# WR-Clocks.net
KiCad netlist of a schematic drawn in Altium Designer
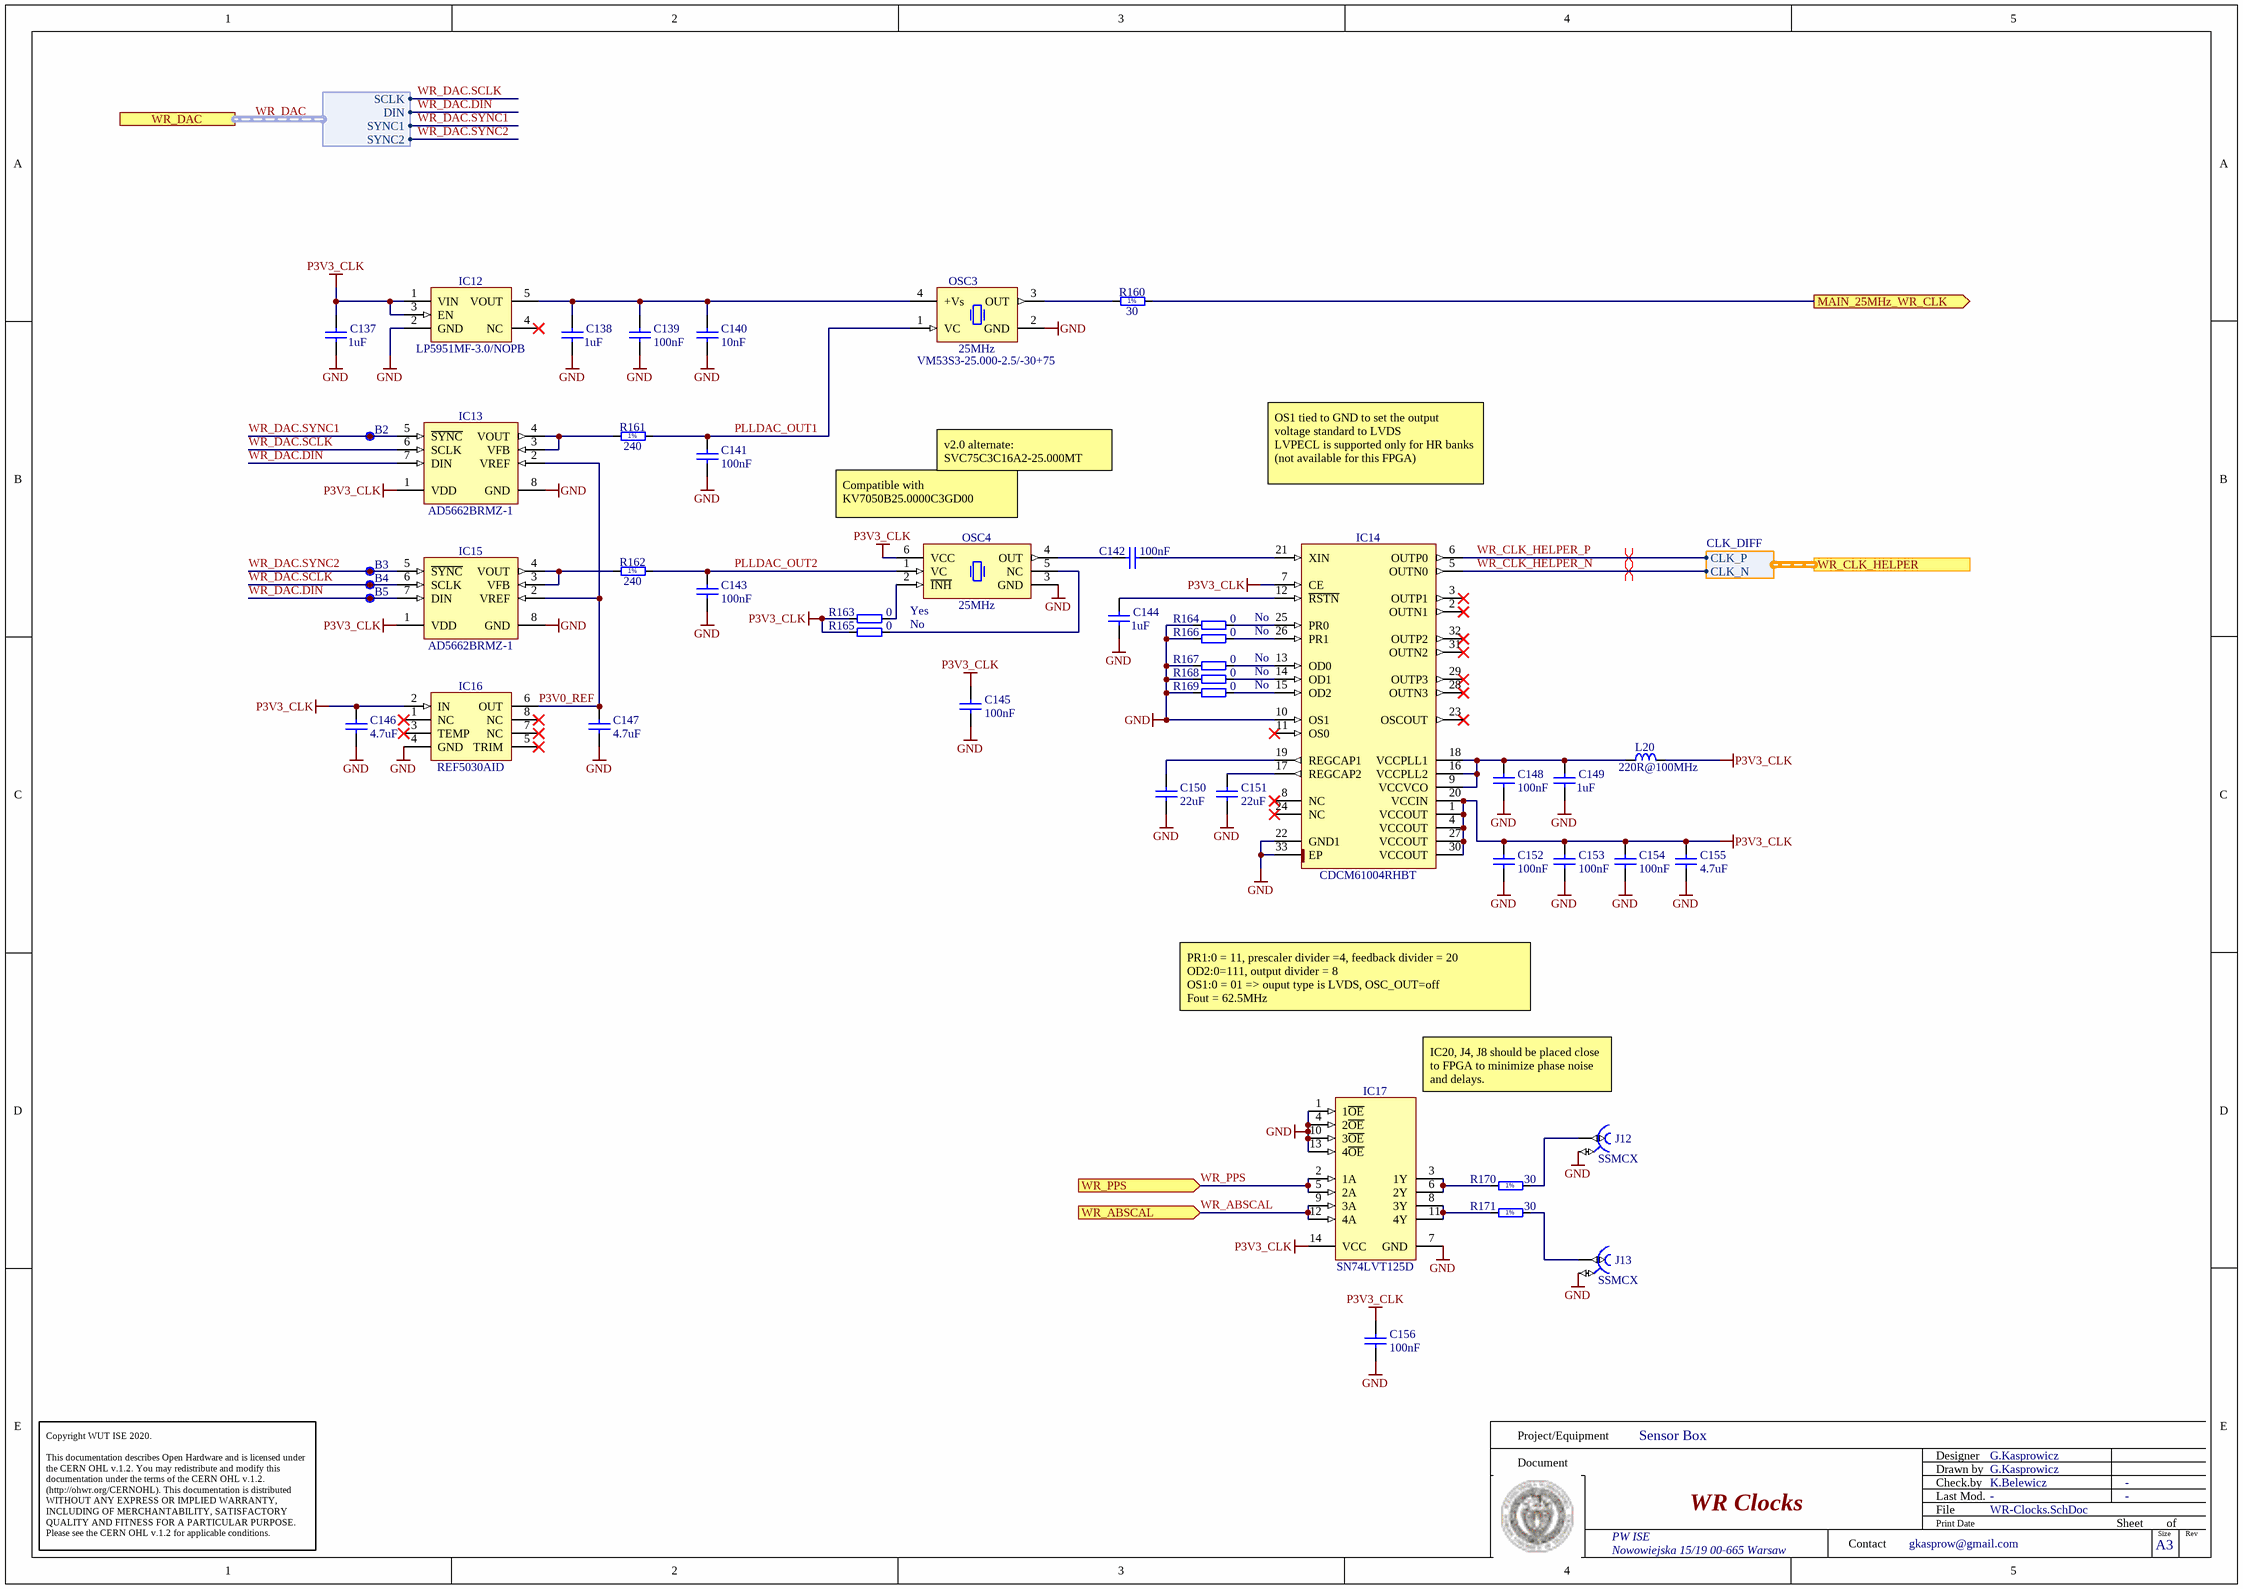
[diagram p0: WR-Clocks.SchDoc]

(export (version "E")
  (design (tool "Eeschema 10.0.6"))
  (components
    (comp (ref "B2")
      (value "SMD Pad")
      (footprint "C100")
      (description "Through Hole Pad")
      (fields (field (name "PART NUMBER") "SMD_PAD_D1MM") (field (name "AUTHOR") "CERN DEM JLC"))
      (libsource (lib "Eletro-mechanical") (part "Single SMD Pad (Round)"))
    )
    (comp (ref "B3")
      (value "SMD Pad")
      (footprint "C100")
      (description "Through Hole Pad")
      (fields (field (name "PART NUMBER") "SMD_PAD_D1MM") (field (name "AUTHOR") "CERN DEM JLC"))
      (libsource (lib "Eletro-mechanical") (part "Single SMD Pad (Round)"))
    )
    (comp (ref "B4")
      (value "SMD Pad")
      (footprint "C100")
      (description "Through Hole Pad")
      (fields (field (name "PART NUMBER") "SMD_PAD_D1MM") (field (name "AUTHOR") "CERN DEM JLC"))
      (libsource (lib "Eletro-mechanical") (part "Single SMD Pad (Round)"))
    )
    (comp (ref "B5")
      (value "SMD Pad")
      (footprint "C100")
      (description "Through Hole Pad")
      (fields (field (name "PART NUMBER") "SMD_PAD_D1MM") (field (name "AUTHOR") "CERN DEM JLC"))
      (libsource (lib "Eletro-mechanical") (part "Single SMD Pad (Round)"))
    )
    (comp (ref "C137")
      (value "1uF")
      (footprint "CAPC1005X55N")
      (description "Non-polarised capacitor")
      (fields
        (field (name "PART NUMBER") "CC0402_1UF_16V_10%_X5R")
        (field (name "VOLTAGE") "16V")
        (field (name "AUTHOR") "CERN DEM JLC")
      )
      (libsource (lib "Capacitors") (part "Capacitor - non polarized"))
    )
    (comp (ref "C138")
      (value "1uF")
      (footprint "CAPC1005X55N")
      (description "Non-polarised capacitor")
      (fields
        (field (name "PART NUMBER") "CC0402_1UF_16V_10%_X5R")
        (field (name "VOLTAGE") "16V")
        (field (name "AUTHOR") "CERN DEM JLC")
      )
      (libsource (lib "Capacitors") (part "Capacitor - non polarized"))
    )
    (comp (ref "C139")
      (value "100nF")
      (footprint "CAPC1005X55N")
      (description "Non-polarised capacitor")
      (fields
        (field (name "PART NUMBER") "CC0402_100NF_16V_10%_X5R")
        (field (name "VOLTAGE") "16V")
        (field (name "AUTHOR") "CERN DEM JLC")
      )
      (libsource (lib "Capacitors") (part "Capacitor - non polarized"))
    )
    (comp (ref "C140")
      (value "10nF")
      (footprint "CAPC1005X55N")
      (description "Non-polarised capacitor")
      (fields
        (field (name "PART NUMBER") "CC0402_10NF_16V_10%_X7R")
        (field (name "VOLTAGE") "16V")
        (field (name "AUTHOR") "CERN DEM JLC")
      )
      (libsource (lib "Capacitors") (part "Capacitor - non polarized"))
    )
    (comp (ref "C141")
      (value "100nF")
      (footprint "CAPC1005X55N")
      (description "Non-polarised capacitor")
      (fields
        (field (name "PART NUMBER") "CC0402_100NF_16V_10%_X5R")
        (field (name "VOLTAGE") "16V")
        (field (name "AUTHOR") "CERN DEM JLC")
      )
      (libsource (lib "Capacitors") (part "Capacitor - non polarized"))
    )
    (comp (ref "C142")
      (value "100nF")
      (footprint "CAPC1005X55N")
      (description "Non-polarised capacitor")
      (fields
        (field (name "PART NUMBER") "CC0402_100NF_16V_10%_X5R")
        (field (name "VOLTAGE") "16V")
        (field (name "AUTHOR") "CERN DEM JLC")
      )
      (libsource (lib "Capacitors") (part "Capacitor - non polarized"))
    )
    (comp (ref "C143")
      (value "100nF")
      (footprint "CAPC1005X55N")
      (description "Non-polarised capacitor")
      (fields
        (field (name "PART NUMBER") "CC0402_100NF_16V_10%_X5R")
        (field (name "VOLTAGE") "16V")
        (field (name "AUTHOR") "CERN DEM JLC")
      )
      (libsource (lib "Capacitors") (part "Capacitor - non polarized"))
    )
    (comp (ref "C144")
      (value "1uF")
      (footprint "CAPC1005X55N")
      (description "Non-polarised capacitor")
      (fields
        (field (name "PART NUMBER") "CC0402_1UF_16V_10%_X5R")
        (field (name "VOLTAGE") "16V")
        (field (name "AUTHOR") "CERN DEM JLC")
      )
      (libsource (lib "Capacitors") (part "Capacitor - non polarized"))
    )
    (comp (ref "C145")
      (value "100nF")
      (footprint "CAPC1005X55N")
      (description "Non-polarised capacitor")
      (fields
        (field (name "PART NUMBER") "CC0402_100NF_16V_10%_X5R")
        (field (name "VOLTAGE") "16V")
        (field (name "AUTHOR") "CERN DEM JLC")
      )
      (libsource (lib "Capacitors") (part "Capacitor - non polarized"))
    )
    (comp (ref "C146")
      (value "4.7uF")
      (footprint "CAPC1005X55N")
      (description "Non-polarised capacitor")
      (fields
        (field (name "PART NUMBER") "CC0402_4.7UF_6.3V_20%_X5R")
        (field (name "VOLTAGE") "6.3V")
        (field (name "AUTHOR") "CERN DEM JLC")
      )
      (libsource (lib "Capacitors") (part "Capacitor - non polarized"))
    )
    (comp (ref "C147")
      (value "4.7uF")
      (footprint "CAPC1005X55N")
      (description "Non-polarised capacitor")
      (fields
        (field (name "PART NUMBER") "CC0402_4.7UF_6.3V_20%_X5R")
        (field (name "VOLTAGE") "6.3V")
        (field (name "AUTHOR") "CERN DEM JLC")
      )
      (libsource (lib "Capacitors") (part "Capacitor - non polarized"))
    )
    (comp (ref "C148")
      (value "100nF")
      (footprint "CAPC1005X55N")
      (description "Non-polarised capacitor")
      (fields
        (field (name "PART NUMBER") "CC0402_100NF_16V_10%_X5R")
        (field (name "VOLTAGE") "16V")
        (field (name "AUTHOR") "CERN DEM JLC")
      )
      (libsource (lib "Capacitors") (part "Capacitor - non polarized"))
    )
    (comp (ref "C149")
      (value "1uF")
      (footprint "CAPC1005X55N")
      (description "Non-polarised capacitor")
      (fields
        (field (name "PART NUMBER") "CC0402_1UF_16V_10%_X5R")
        (field (name "VOLTAGE") "16V")
        (field (name "AUTHOR") "CERN DEM JLC")
      )
      (libsource (lib "Capacitors") (part "Capacitor - non polarized"))
    )
    (comp (ref "C150")
      (value "22uF")
      (footprint "CAPC1709X100N")
      (description "Non-polarised capacitor")
      (fields
        (field (name "PART NUMBER") "CC0603_22UF_6.3V_20%_X5R")
        (field (name "VOLTAGE") "6.3V")
        (field (name "AUTHOR") "CERN DEM JLC")
      )
      (libsource (lib "Capacitors") (part "Capacitor - non polarized"))
    )
    (comp (ref "C151")
      (value "22uF")
      (footprint "CAPC1709X100N")
      (description "Non-polarised capacitor")
      (fields
        (field (name "PART NUMBER") "CC0603_22UF_6.3V_20%_X5R")
        (field (name "VOLTAGE") "6.3V")
        (field (name "AUTHOR") "CERN DEM JLC")
      )
      (libsource (lib "Capacitors") (part "Capacitor - non polarized"))
    )
    (comp (ref "C152")
      (value "100nF")
      (footprint "CAPC1005X55N")
      (description "Non-polarised capacitor")
      (fields
        (field (name "PART NUMBER") "CC0402_100NF_16V_10%_X5R")
        (field (name "VOLTAGE") "16V")
        (field (name "AUTHOR") "CERN DEM JLC")
      )
      (libsource (lib "Capacitors") (part "Capacitor - non polarized"))
    )
    (comp (ref "C153")
      (value "100nF")
      (footprint "CAPC1005X55N")
      (description "Non-polarised capacitor")
      (fields
        (field (name "PART NUMBER") "CC0402_100NF_16V_10%_X5R")
        (field (name "VOLTAGE") "16V")
        (field (name "AUTHOR") "CERN DEM JLC")
      )
      (libsource (lib "Capacitors") (part "Capacitor - non polarized"))
    )
    (comp (ref "C154")
      (value "100nF")
      (footprint "CAPC1005X55N")
      (description "Non-polarised capacitor")
      (fields
        (field (name "PART NUMBER") "CC0402_100NF_16V_10%_X5R")
        (field (name "VOLTAGE") "16V")
        (field (name "AUTHOR") "CERN DEM JLC")
      )
      (libsource (lib "Capacitors") (part "Capacitor - non polarized"))
    )
    (comp (ref "C155")
      (value "4.7uF")
      (footprint "CAPC1005X55N")
      (description "Non-polarised capacitor")
      (fields
        (field (name "PART NUMBER") "CC0402_4.7UF_6.3V_20%_X5R")
        (field (name "VOLTAGE") "6.3V")
        (field (name "AUTHOR") "CERN DEM JLC")
      )
      (libsource (lib "Capacitors") (part "Capacitor - non polarized"))
    )
    (comp (ref "C156")
      (value "100nF")
      (footprint "CAPC1005X55N")
      (description "Non-polarised capacitor")
      (fields
        (field (name "PART NUMBER") "CC0402_100NF_16V_10%_X5R")
        (field (name "VOLTAGE") "16V")
        (field (name "AUTHOR") "CERN DEM JLC")
      )
      (libsource (lib "Capacitors") (part "Capacitor - non polarized"))
    )
    (comp (ref "IC12")
      (value "LP5951MF-3.0/NOPB")
      (footprint "SOT95P284X122-5N")
      (description "150mA Micropower Low-Dropout CMOS Voltage Regulator")
      (fields (field (name "MANUFACTURER") "NATIONAL SEMICONDUCTOR") (field (name "AUTHOR") "CERN DEM JLC"))
      (libsource (lib "ICs And Semiconductors") (part "LP5951"))
    )
    (comp (ref "IC13")
      (value "AD5662BRMZ-1")
      (footprint "SOP65P490X110-8N")
      (description "2.7V to 5.5V, 250uA, Rail-to-Rail Output 16-Bit nanoDAC")
      (fields (field (name "MANUFACTURER") "ANALOG DEVICES") (field (name "AUTHOR") "CERN DEM JLC"))
      (libsource (lib "ICs And Semiconductors") (part "AD5662"))
    )
    (comp (ref "IC14")
      (value "CDCM61004RHBT")
      (footprint "QFN50P500X500X100-33N-S355")
      (description "Four Output, Integrated VCO, Low-Jitter Clock Generator")
      (fields (field (name "MANUFACTURER") "TEXAS INSTRUMENTS") (field (name "AUTHOR") "CERN DEM JLC"))
      (libsource (lib "ICs And Semiconductors") (part "CDCM61004RHB"))
    )
    (comp (ref "IC15")
      (value "AD5662BRMZ-1")
      (footprint "SOP65P490X110-8N")
      (description "2.7V to 5.5V, 250uA, Rail-to-Rail Output 16-Bit nanoDAC")
      (fields (field (name "MANUFACTURER") "ANALOG DEVICES") (field (name "AUTHOR") "CERN DEM JLC"))
      (libsource (lib "ICs And Semiconductors") (part "AD5662"))
    )
    (comp (ref "IC16")
      (value "REF5030AID")
      (footprint "SOIC127P600X175-8N")
      (description "Low-Noise, Very Low Drift, Precision Voltage Reference")
      (fields (field (name "MANUFACTURER") "TEXAS INSTRUMENTS") (field (name "AUTHOR") "CERN DEM MR"))
      (libsource (lib "ICs And Semiconductors") (part "REF50"))
    )
    (comp (ref "IC17")
      (value "SN74LVT125D")
      (footprint "SOIC127P600X175-14N")
      (description "Quadruple Bus Buffer with 3-State Outputs")
      (fields (field (name "MANUFACTURER") "TEXAS INSTRUMENTS") (field (name "AUTHOR") "CERN DEM JLC"))
      (libsource (lib "ICs And Semiconductors") (part "74125"))
    )
    (comp (ref "J12")
      (value "SSMCX")
      (footprint "MOLEX_73413-0040")
      (fields
        (field (name "PART NUMBER") "MOLEX_73413-0040")
        (field (name "MANUFACTURER") "MOLEX")
        (field (name "MANUFACTURER PART NUMBER") "73413-0040")
        (field (name "AUTHOR") "CERN DEM JLC")
      )
      (libsource (lib "Connectors") (part "Coax_1Female_1Shield"))
    )
    (comp (ref "J13")
      (value "SSMCX")
      (footprint "MOLEX_73413-0040")
      (fields
        (field (name "PART NUMBER") "MOLEX_73413-0040")
        (field (name "MANUFACTURER") "MOLEX")
        (field (name "MANUFACTURER PART NUMBER") "73413-0040")
        (field (name "AUTHOR") "CERN DEM JLC")
      )
      (libsource (lib "Connectors") (part "Coax_1Female_1Shield"))
    )
    (comp (ref "L20")
      (value "220R@100MHz")
      (footprint "INDC2012X105N")
      (description "Inductor")
      (fields
        (field (name "PART NUMBER") "IND0805_MURATA_BLM21PG221SN1D")
        (field (name "POWER") "2A")
        (field (name "AUTHOR") "CERN DEM JLC")
      )
      (libsource (lib "Inductors & Transformers") (part "Inductor"))
    )
    (comp (ref "OSC3")
      (value "25MHz")
      (footprint "OSCCC320X500X160-4N")
      (description "Oscillator 4 pins 1=VC 2=GND 3=OUT 4=+Vs")
      (fields
        (field (name "PART NUMBER") "OSC_25MHZ_MERCURY_VM53S3-25.000-2.5/-30+75")
        (field (name "MANUFACTURER") "MERCURY ELECTRONICS")
        (field (name "MANUFACTURER PART NUMBER") "VM53S3-25.000-2.5/-30+75")
        (field (name "AUTHOR") "CERN DEM JLC")
      )
      (libsource (lib "ICs And Semiconductors") (part "Oscillator 1VC 2GND 3OUT 4+Vs"))
    )
    (comp (ref "OSC4")
      (value "25MHz")
      (footprint "OSC_KYOCERA_KV7050B-C3")
      (description "Oscillator KYOCERA")
      (fields
        (field (name "PART NUMBER") "OSC_25MHZ_KYOCERA_KV7050B25.0000C3GD00")
        (field (name "MANUFACTURER") "KYOCERA")
        (field (name "AUTHOR") "CERN DEM MR")
      )
      (libsource (lib "ICs And Semiconductors") (part "Oscillator KYOCERA_KV7050B-C3"))
    )
    (comp (ref "R160")
      (value "30")
      (footprint "RESC1005X40N")
      (description "Resistor - 1%")
      (fields
        (field (name "PART NUMBER") "R0402_30R_1%_0.0625W_100PPM")
        (field (name "POWER") "0.0625W")
        (field (name "AUTHOR") "CERN DEM JLC")
      )
      (libsource (lib "Resistors") (part "Resistor - 1%"))
    )
    (comp (ref "R161")
      (value "240")
      (footprint "RESC1005X40N")
      (description "Resistor - 1%")
      (fields
        (field (name "PART NUMBER") "R0402_240R_1%_0.0625W_100PPM")
        (field (name "POWER") "0.0625W")
        (field (name "AUTHOR") "CERN DEM JLC")
      )
      (libsource (lib "Resistors") (part "Resistor - 1%"))
    )
    (comp (ref "R162")
      (value "240")
      (footprint "RESC1005X40N")
      (description "Resistor - 1%")
      (fields
        (field (name "PART NUMBER") "R0402_240R_1%_0.0625W_100PPM")
        (field (name "POWER") "0.0625W")
        (field (name "AUTHOR") "CERN DEM JLC")
      )
      (libsource (lib "Resistors") (part "Resistor - 1%"))
    )
    (comp (ref "R163")
      (value "0")
      (footprint "RESC1005X40N")
      (description "Resistor")
      (fields
        (field (name "PART NUMBER") "R0402_0R_JUMPER")
        (field (name "MANUFACTURER") "GENERIC")
        (field (name "MOUNTED") "Yes")
        (field (name "AUTHOR") "CERN DEM JLC")
      )
      (libsource (lib "Resistors") (part "Resistor"))
    )
    (comp (ref "R164")
      (value "0")
      (footprint "RESC1005X40N")
      (description "Resistor")
      (fields
        (field (name "PART NUMBER") "R0402_0R_JUMPER")
        (field (name "MANUFACTURER") "GENERIC")
        (field (name "MOUNTED") "No")
        (field (name "AUTHOR") "CERN DEM JLC")
      )
      (libsource (lib "Resistors") (part "Resistor"))
    )
    (comp (ref "R165")
      (value "0")
      (footprint "RESC1005X40N")
      (description "Resistor")
      (fields
        (field (name "PART NUMBER") "R0402_0R_JUMPER")
        (field (name "MANUFACTURER") "GENERIC")
        (field (name "MOUNTED") "No")
        (field (name "AUTHOR") "CERN DEM JLC")
      )
      (libsource (lib "Resistors") (part "Resistor"))
    )
    (comp (ref "R166")
      (value "0")
      (footprint "RESC1005X40N")
      (description "Resistor")
      (fields
        (field (name "PART NUMBER") "R0402_0R_JUMPER")
        (field (name "MANUFACTURER") "GENERIC")
        (field (name "MOUNTED") "No")
        (field (name "AUTHOR") "CERN DEM JLC")
      )
      (libsource (lib "Resistors") (part "Resistor"))
    )
    (comp (ref "R167")
      (value "0")
      (footprint "RESC1005X40N")
      (description "Resistor")
      (fields
        (field (name "PART NUMBER") "R0402_0R_JUMPER")
        (field (name "MANUFACTURER") "GENERIC")
        (field (name "MOUNTED") "No")
        (field (name "AUTHOR") "CERN DEM JLC")
      )
      (libsource (lib "Resistors") (part "Resistor"))
    )
    (comp (ref "R168")
      (value "0")
      (footprint "RESC1005X40N")
      (description "Resistor")
      (fields
        (field (name "PART NUMBER") "R0402_0R_JUMPER")
        (field (name "MANUFACTURER") "GENERIC")
        (field (name "MOUNTED") "No")
        (field (name "AUTHOR") "CERN DEM JLC")
      )
      (libsource (lib "Resistors") (part "Resistor"))
    )
    (comp (ref "R169")
      (value "0")
      (footprint "RESC1005X40N")
      (description "Resistor")
      (fields
        (field (name "PART NUMBER") "R0402_0R_JUMPER")
        (field (name "MANUFACTURER") "GENERIC")
        (field (name "MOUNTED") "No")
        (field (name "AUTHOR") "CERN DEM JLC")
      )
      (libsource (lib "Resistors") (part "Resistor"))
    )
    (comp (ref "R170")
      (value "30")
      (footprint "RESC1005X40N")
      (description "Resistor - 1%")
      (fields
        (field (name "PART NUMBER") "R0402_30R_1%_0.0625W_100PPM")
        (field (name "POWER") "0.0625W")
        (field (name "AUTHOR") "CERN DEM JLC")
      )
      (libsource (lib "Resistors") (part "Resistor - 1%"))
    )
    (comp (ref "R171")
      (value "30")
      (footprint "RESC1005X40N")
      (description "Resistor - 1%")
      (fields
        (field (name "PART NUMBER") "R0402_30R_1%_0.0625W_100PPM")
        (field (name "POWER") "0.0625W")
        (field (name "AUTHOR") "CERN DEM JLC")
      )
      (libsource (lib "Resistors") (part "Resistor - 1%"))
    )
  )
  (nets
    (net (code "3") (name "/MAIN_25MHz_WR_CLK") (class "Default")
      (node (ref "R160") (pin "2") (pinfunction "2_2") (pintype "passive"))
    )
    (net (code "4") (name "/P3V0_REF") (class "Default")
      (node (ref "C147") (pin "2") (pinfunction "2_2") (pintype "passive"))
      (node (ref "IC13") (pin "2") (pinfunction "VREF_2") (pintype "input"))
      (node (ref "IC15") (pin "2") (pinfunction "VREF_2") (pintype "input"))
      (node (ref "IC16") (pin "6") (pinfunction "OUT_6") (pintype "power_in"))
    )
    (net (code "5") (name "/PLLDAC_OUT1") (class "Default")
      (node (ref "C141") (pin "2") (pinfunction "2_2") (pintype "passive"))
      (node (ref "OSC3") (pin "1") (pinfunction "VC_1") (pintype "input"))
      (node (ref "R161") (pin "2") (pinfunction "2_2") (pintype "passive"))
    )
    (net (code "6") (name "/PLLDAC_OUT2") (class "Default")
      (node (ref "C143") (pin "2") (pinfunction "2_2") (pintype "passive"))
      (node (ref "OSC4") (pin "1") (pinfunction "VC_1") (pintype "input"))
      (node (ref "R162") (pin "2") (pinfunction "2_2") (pintype "passive"))
    )
    (net (code "7") (name "/WR_ABSCAL") (class "Default")
      (node (ref "IC17") (pin "12") (pinfunction "4A_12") (pintype "input"))
      (node (ref "IC17") (pin "9") (pinfunction "3A_9") (pintype "input"))
    )
    (net (code "8") (name "/WR_CLK_HELPER_N") (class "Default")
      (node (ref "IC14") (pin "5") (pinfunction "OUTN0_5") (pintype "output"))
    )
    (net (code "9") (name "/WR_CLK_HELPER_P") (class "Default")
      (node (ref "IC14") (pin "6") (pinfunction "OUTP0_6") (pintype "output"))
    )
    (net (code "10") (name "/WR_DAC.DIN") (class "Default")
      (node (ref "B5") (pin "1") (pinfunction "1_1") (pintype "bidirectional"))
      (node (ref "IC13") (pin "7") (pinfunction "DIN_7") (pintype "input"))
      (node (ref "IC15") (pin "7") (pinfunction "DIN_7") (pintype "input"))
    )
    (net (code "11") (name "/WR_DAC.SCLK") (class "Default")
      (node (ref "B4") (pin "1") (pinfunction "1_1") (pintype "bidirectional"))
      (node (ref "IC13") (pin "6") (pinfunction "SCLK_6") (pintype "input"))
      (node (ref "IC15") (pin "6") (pinfunction "SCLK_6") (pintype "input"))
    )
    (net (code "12") (name "/WR_DAC.SYNC1") (class "Default")
      (node (ref "B2") (pin "1") (pinfunction "1_1") (pintype "bidirectional"))
      (node (ref "IC13") (pin "5") (pinfunction "~{SYNC}_5") (pintype "input"))
    )
    (net (code "13") (name "/WR_DAC.SYNC2") (class "Default")
      (node (ref "B3") (pin "1") (pinfunction "1_1") (pintype "bidirectional"))
      (node (ref "IC15") (pin "5") (pinfunction "~{SYNC}_5") (pintype "input"))
    )
    (net (code "15") (name "/WR_PPS") (class "Default")
      (node (ref "IC17") (pin "2") (pinfunction "1A_2") (pintype "input"))
      (node (ref "IC17") (pin "5") (pinfunction "2A_5") (pintype "input"))
    )
    (net (code "17") (name "GND") (class "Default")
      (node (ref "C137") (pin "1") (pinfunction "1_1") (pintype "passive"))
      (node (ref "C138") (pin "1") (pinfunction "1_1") (pintype "passive"))
      (node (ref "C139") (pin "1") (pinfunction "1_1") (pintype "passive"))
      (node (ref "C140") (pin "1") (pinfunction "1_1") (pintype "passive"))
      (node (ref "C141") (pin "1") (pinfunction "1_1") (pintype "passive"))
      (node (ref "C143") (pin "1") (pinfunction "1_1") (pintype "passive"))
      (node (ref "C144") (pin "1") (pinfunction "1_1") (pintype "passive"))
      (node (ref "C145") (pin "1") (pinfunction "1_1") (pintype "passive"))
      (node (ref "C146") (pin "1") (pinfunction "1_1") (pintype "passive"))
      (node (ref "C147") (pin "1") (pinfunction "1_1") (pintype "passive"))
      (node (ref "C148") (pin "1") (pinfunction "1_1") (pintype "passive"))
      (node (ref "C149") (pin "1") (pinfunction "1_1") (pintype "passive"))
      (node (ref "C150") (pin "1") (pinfunction "1_1") (pintype "passive"))
      (node (ref "C151") (pin "1") (pinfunction "1_1") (pintype "passive"))
      (node (ref "C152") (pin "1") (pinfunction "1_1") (pintype "passive"))
      (node (ref "C153") (pin "1") (pinfunction "1_1") (pintype "passive"))
      (node (ref "C154") (pin "1") (pinfunction "1_1") (pintype "passive"))
      (node (ref "C155") (pin "1") (pinfunction "1_1") (pintype "passive"))
      (node (ref "C156") (pin "1") (pinfunction "1_1") (pintype "passive"))
      (node (ref "IC12") (pin "2") (pinfunction "GND_2") (pintype "power_in"))
      (node (ref "IC13") (pin "8") (pinfunction "GND_8") (pintype "power_in"))
      (node (ref "IC14") (pin "10") (pinfunction "OS1_10") (pintype "input"))
      (node (ref "IC14") (pin "22") (pinfunction "GND1_22") (pintype "power_in"))
      (node (ref "IC14") (pin "33") (pinfunction "EP_33") (pintype "power_in"))
      (node (ref "IC15") (pin "8") (pinfunction "GND_8") (pintype "power_in"))
      (node (ref "IC16") (pin "4") (pinfunction "GND_4") (pintype "power_in"))
      (node (ref "IC17") (pin "1") (pinfunction "1~{OE}_1") (pintype "input"))
      (node (ref "IC17") (pin "10") (pinfunction "3~{OE}_10") (pintype "input"))
      (node (ref "IC17") (pin "13") (pinfunction "4~{OE}_13") (pintype "input"))
      (node (ref "IC17") (pin "4") (pinfunction "2~{OE}_4") (pintype "input"))
      (node (ref "IC17") (pin "7") (pinfunction "GND_7") (pintype "power_in"))
      (node (ref "J12") (pin "2") (pinfunction "2_2") (pintype "bidirectional"))
      (node (ref "J13") (pin "2") (pinfunction "2_2") (pintype "bidirectional"))
      (node (ref "OSC3") (pin "2") (pinfunction "GND_2") (pintype "power_in"))
      (node (ref "OSC4") (pin "3") (pinfunction "GND_3") (pintype "power_in"))
      (node (ref "R164") (pin "1") (pinfunction "1_1") (pintype "passive"))
      (node (ref "R166") (pin "1") (pinfunction "1_1") (pintype "passive"))
      (node (ref "R167") (pin "1") (pinfunction "1_1") (pintype "passive"))
      (node (ref "R168") (pin "1") (pinfunction "1_1") (pintype "passive"))
      (node (ref "R169") (pin "1") (pinfunction "1_1") (pintype "passive"))
    )
    (net (code "18") (name "Net-(IC12-VOUT)") (class "Default")
      (node (ref "C138") (pin "2") (pinfunction "2_2") (pintype "passive"))
      (node (ref "C139") (pin "2") (pinfunction "2_2") (pintype "passive"))
      (node (ref "C140") (pin "2") (pinfunction "2_2") (pintype "passive"))
      (node (ref "IC12") (pin "5") (pinfunction "VOUT_5") (pintype "power_in"))
      (node (ref "OSC3") (pin "4") (pinfunction "+Vs_4") (pintype "power_in"))
    )
    (net (code "19") (name "Net-(IC13-VFB)") (class "Default")
      (node (ref "IC13") (pin "3") (pinfunction "VFB_3") (pintype "input"))
      (node (ref "IC13") (pin "4") (pinfunction "VOUT_4") (pintype "output"))
      (node (ref "R161") (pin "1") (pinfunction "1_1") (pintype "passive"))
    )
    (net (code "20") (name "Net-(IC14-OD0)") (class "Default")
      (node (ref "IC14") (pin "13") (pinfunction "OD0_13") (pintype "input"))
      (node (ref "R167") (pin "2") (pinfunction "2_2") (pintype "passive"))
    )
    (net (code "21") (name "Net-(IC14-OD1)") (class "Default")
      (node (ref "IC14") (pin "14") (pinfunction "OD1_14") (pintype "input"))
      (node (ref "R168") (pin "2") (pinfunction "2_2") (pintype "passive"))
    )
    (net (code "22") (name "Net-(IC14-OD2)") (class "Default")
      (node (ref "IC14") (pin "15") (pinfunction "OD2_15") (pintype "input"))
      (node (ref "R169") (pin "2") (pinfunction "2_2") (pintype "passive"))
    )
    (net (code "23") (name "Net-(IC14-PR0)") (class "Default")
      (node (ref "IC14") (pin "25") (pinfunction "PR0_25") (pintype "input"))
      (node (ref "R164") (pin "2") (pinfunction "2_2") (pintype "passive"))
    )
    (net (code "24") (name "Net-(IC14-PR1)") (class "Default")
      (node (ref "IC14") (pin "26") (pinfunction "PR1_26") (pintype "input"))
      (node (ref "R166") (pin "2") (pinfunction "2_2") (pintype "passive"))
    )
    (net (code "25") (name "Net-(IC14-REGCAP1)") (class "Default")
      (node (ref "C150") (pin "2") (pinfunction "2_2") (pintype "passive"))
      (node (ref "IC14") (pin "19") (pinfunction "REGCAP1_19") (pintype "output"))
    )
    (net (code "26") (name "Net-(IC14-REGCAP2)") (class "Default")
      (node (ref "C151") (pin "2") (pinfunction "2_2") (pintype "passive"))
      (node (ref "IC14") (pin "17") (pinfunction "REGCAP2_17") (pintype "output"))
    )
    (net (code "27") (name "Net-(IC14-VCCPLL1)") (class "Default")
      (node (ref "C148") (pin "2") (pinfunction "2_2") (pintype "passive"))
      (node (ref "C149") (pin "2") (pinfunction "2_2") (pintype "passive"))
      (node (ref "IC14") (pin "16") (pinfunction "VCCPLL2_16") (pintype "power_in"))
      (node (ref "IC14") (pin "18") (pinfunction "VCCPLL1_18") (pintype "power_in"))
      (node (ref "IC14") (pin "9") (pinfunction "VCCVCO_9") (pintype "power_in"))
      (node (ref "L20") (pin "1") (pinfunction "1_1") (pintype "passive"))
    )
    (net (code "28") (name "Net-(IC14-XIN)") (class "Default")
      (node (ref "C142") (pin "1") (pinfunction "1_1") (pintype "passive"))
      (node (ref "IC14") (pin "21") (pinfunction "XIN_21") (pintype "input"))
    )
    (net (code "29") (name "Net-(IC14-~{RSTN})") (class "Default")
      (node (ref "C144") (pin "2") (pinfunction "2_2") (pintype "passive"))
      (node (ref "IC14") (pin "12") (pinfunction "~{RSTN}_12") (pintype "input"))
    )
    (net (code "30") (name "Net-(IC15-VFB)") (class "Default")
      (node (ref "IC15") (pin "3") (pinfunction "VFB_3") (pintype "input"))
      (node (ref "IC15") (pin "4") (pinfunction "VOUT_4") (pintype "output"))
      (node (ref "R162") (pin "1") (pinfunction "1_1") (pintype "passive"))
    )
    (net (code "31") (name "Net-(IC17-1Y)") (class "Default")
      (node (ref "IC17") (pin "3") (pinfunction "1Y_3") (pintype "tri_state"))
      (node (ref "IC17") (pin "6") (pinfunction "2Y_6") (pintype "tri_state"))
      (node (ref "R170") (pin "1") (pinfunction "1_1") (pintype "passive"))
    )
    (net (code "32") (name "Net-(IC17-3Y)") (class "Default")
      (node (ref "IC17") (pin "11") (pinfunction "4Y_11") (pintype "tri_state"))
      (node (ref "IC17") (pin "8") (pinfunction "3Y_8") (pintype "tri_state"))
      (node (ref "R171") (pin "1") (pinfunction "1_1") (pintype "passive"))
    )
    (net (code "33") (name "Net-(J12-Pad1)") (class "Default")
      (node (ref "J12") (pin "1") (pinfunction "1_1") (pintype "bidirectional"))
      (node (ref "R170") (pin "2") (pinfunction "2_2") (pintype "passive"))
    )
    (net (code "34") (name "Net-(J13-Pad1)") (class "Default")
      (node (ref "J13") (pin "1") (pinfunction "1_1") (pintype "bidirectional"))
      (node (ref "R171") (pin "2") (pinfunction "2_2") (pintype "passive"))
    )
    (net (code "35") (name "Net-(OSC3-OUT)") (class "Default")
      (node (ref "OSC3") (pin "3") (pinfunction "OUT_3") (pintype "output"))
      (node (ref "R160") (pin "1") (pinfunction "1_1") (pintype "passive"))
    )
    (net (code "36") (name "Net-(OSC4-NC)") (class "Default")
      (node (ref "OSC4") (pin "5") (pinfunction "NC_5") (pintype "passive"))
      (node (ref "R165") (pin "2") (pinfunction "2_2") (pintype "passive"))
    )
    (net (code "37") (name "Net-(OSC4-OUT)") (class "Default")
      (node (ref "C142") (pin "2") (pinfunction "2_2") (pintype "passive"))
      (node (ref "OSC4") (pin "4") (pinfunction "OUT_4") (pintype "output"))
    )
    (net (code "38") (name "Net-(OSC4-~{INH})") (class "Default")
      (node (ref "OSC4") (pin "2") (pinfunction "~{INH}_2") (pintype "input"))
      (node (ref "R163") (pin "2") (pinfunction "2_2") (pintype "passive"))
    )
    (net (code "39") (name "P3V3_CLK") (class "Default")
      (node (ref "C137") (pin "2") (pinfunction "2_2") (pintype "passive"))
      (node (ref "C145") (pin "2") (pinfunction "2_2") (pintype "passive"))
      (node (ref "C146") (pin "2") (pinfunction "2_2") (pintype "passive"))
      (node (ref "C152") (pin "2") (pinfunction "2_2") (pintype "passive"))
      (node (ref "C153") (pin "2") (pinfunction "2_2") (pintype "passive"))
      (node (ref "C154") (pin "2") (pinfunction "2_2") (pintype "passive"))
      (node (ref "C155") (pin "2") (pinfunction "2_2") (pintype "passive"))
      (node (ref "C156") (pin "2") (pinfunction "2_2") (pintype "passive"))
      (node (ref "IC12") (pin "1") (pinfunction "VIN_1") (pintype "power_in"))
      (node (ref "IC12") (pin "3") (pinfunction "EN_3") (pintype "input"))
      (node (ref "IC13") (pin "1") (pinfunction "VDD_1") (pintype "power_in"))
      (node (ref "IC14") (pin "1") (pinfunction "VCCOUT_1") (pintype "power_in"))
      (node (ref "IC14") (pin "20") (pinfunction "VCCIN_20") (pintype "power_in"))
      (node (ref "IC14") (pin "27") (pinfunction "VCCOUT_27") (pintype "power_in"))
      (node (ref "IC14") (pin "30") (pinfunction "VCCOUT_30") (pintype "power_in"))
      (node (ref "IC14") (pin "4") (pinfunction "VCCOUT_4") (pintype "power_in"))
      (node (ref "IC14") (pin "7") (pinfunction "CE_7") (pintype "input"))
      (node (ref "IC15") (pin "1") (pinfunction "VDD_1") (pintype "power_in"))
      (node (ref "IC16") (pin "2") (pinfunction "IN_2") (pintype "input"))
      (node (ref "IC17") (pin "14") (pinfunction "VCC_14") (pintype "power_in"))
      (node (ref "L20") (pin "2") (pinfunction "2_2") (pintype "passive"))
      (node (ref "OSC4") (pin "6") (pinfunction "VCC_6") (pintype "power_in"))
      (node (ref "R163") (pin "1") (pinfunction "1_1") (pintype "passive"))
      (node (ref "R165") (pin "1") (pinfunction "1_1") (pintype "passive"))
    )
    (net (code "40") (name "unconnected-(IC12-NC-Pad4)") (class "Default")
      (node (ref "IC12") (pin "4") (pinfunction "NC_4") (pintype "passive+no_connect"))
    )
    (net (code "41") (name "unconnected-(IC14-NC-Pad8)") (class "Default")
      (node (ref "IC14") (pin "8") (pinfunction "NC_8") (pintype "passive+no_connect"))
    )
    (net (code "42") (name "unconnected-(IC14-NC-Pad24)") (class "Default")
      (node (ref "IC14") (pin "24") (pinfunction "NC_24") (pintype "passive+no_connect"))
    )
    (net (code "43") (name "unconnected-(IC14-OS0-Pad11)") (class "Default")
      (node (ref "IC14") (pin "11") (pinfunction "OS0_11") (pintype "input+no_connect"))
    )
    (net (code "44") (name "unconnected-(IC14-OSCOUT-Pad23)") (class "Default")
      (node (ref "IC14") (pin "23") (pinfunction "OSCOUT_23") (pintype "output+no_connect"))
    )
    (net (code "45") (name "unconnected-(IC14-OUTN1-Pad2)") (class "Default")
      (node (ref "IC14") (pin "2") (pinfunction "OUTN1_2") (pintype "output+no_connect"))
    )
    (net (code "46") (name "unconnected-(IC14-OUTN2-Pad31)") (class "Default")
      (node (ref "IC14") (pin "31") (pinfunction "OUTN2_31") (pintype "output+no_connect"))
    )
    (net (code "47") (name "unconnected-(IC14-OUTN3-Pad28)") (class "Default")
      (node (ref "IC14") (pin "28") (pinfunction "OUTN3_28") (pintype "output+no_connect"))
    )
    (net (code "48") (name "unconnected-(IC14-OUTP1-Pad3)") (class "Default")
      (node (ref "IC14") (pin "3") (pinfunction "OUTP1_3") (pintype "output+no_connect"))
    )
    (net (code "49") (name "unconnected-(IC14-OUTP2-Pad32)") (class "Default")
      (node (ref "IC14") (pin "32") (pinfunction "OUTP2_32") (pintype "output+no_connect"))
    )
    (net (code "50") (name "unconnected-(IC14-OUTP3-Pad29)") (class "Default")
      (node (ref "IC14") (pin "29") (pinfunction "OUTP3_29") (pintype "output+no_connect"))
    )
    (net (code "51") (name "unconnected-(IC16-NC-Pad1)") (class "Default")
      (node (ref "IC16") (pin "1") (pinfunction "NC_1") (pintype "passive+no_connect"))
    )
    (net (code "52") (name "unconnected-(IC16-NC-Pad7)") (class "Default")
      (node (ref "IC16") (pin "7") (pinfunction "NC_7") (pintype "passive+no_connect"))
    )
    (net (code "53") (name "unconnected-(IC16-NC-Pad8)") (class "Default")
      (node (ref "IC16") (pin "8") (pinfunction "NC_8") (pintype "passive+no_connect"))
    )
    (net (code "54") (name "unconnected-(IC16-TEMP-Pad3)") (class "Default")
      (node (ref "IC16") (pin "3") (pinfunction "TEMP_3") (pintype "passive+no_connect"))
    )
    (net (code "55") (name "unconnected-(IC16-TRIM-Pad5)") (class "Default")
      (node (ref "IC16") (pin "5") (pinfunction "TRIM_5") (pintype "passive+no_connect"))
    )
  )
)
